# SCH_starcard_2025-07-30.net
KiCad netlist of a schematic drawn in EasyEDA
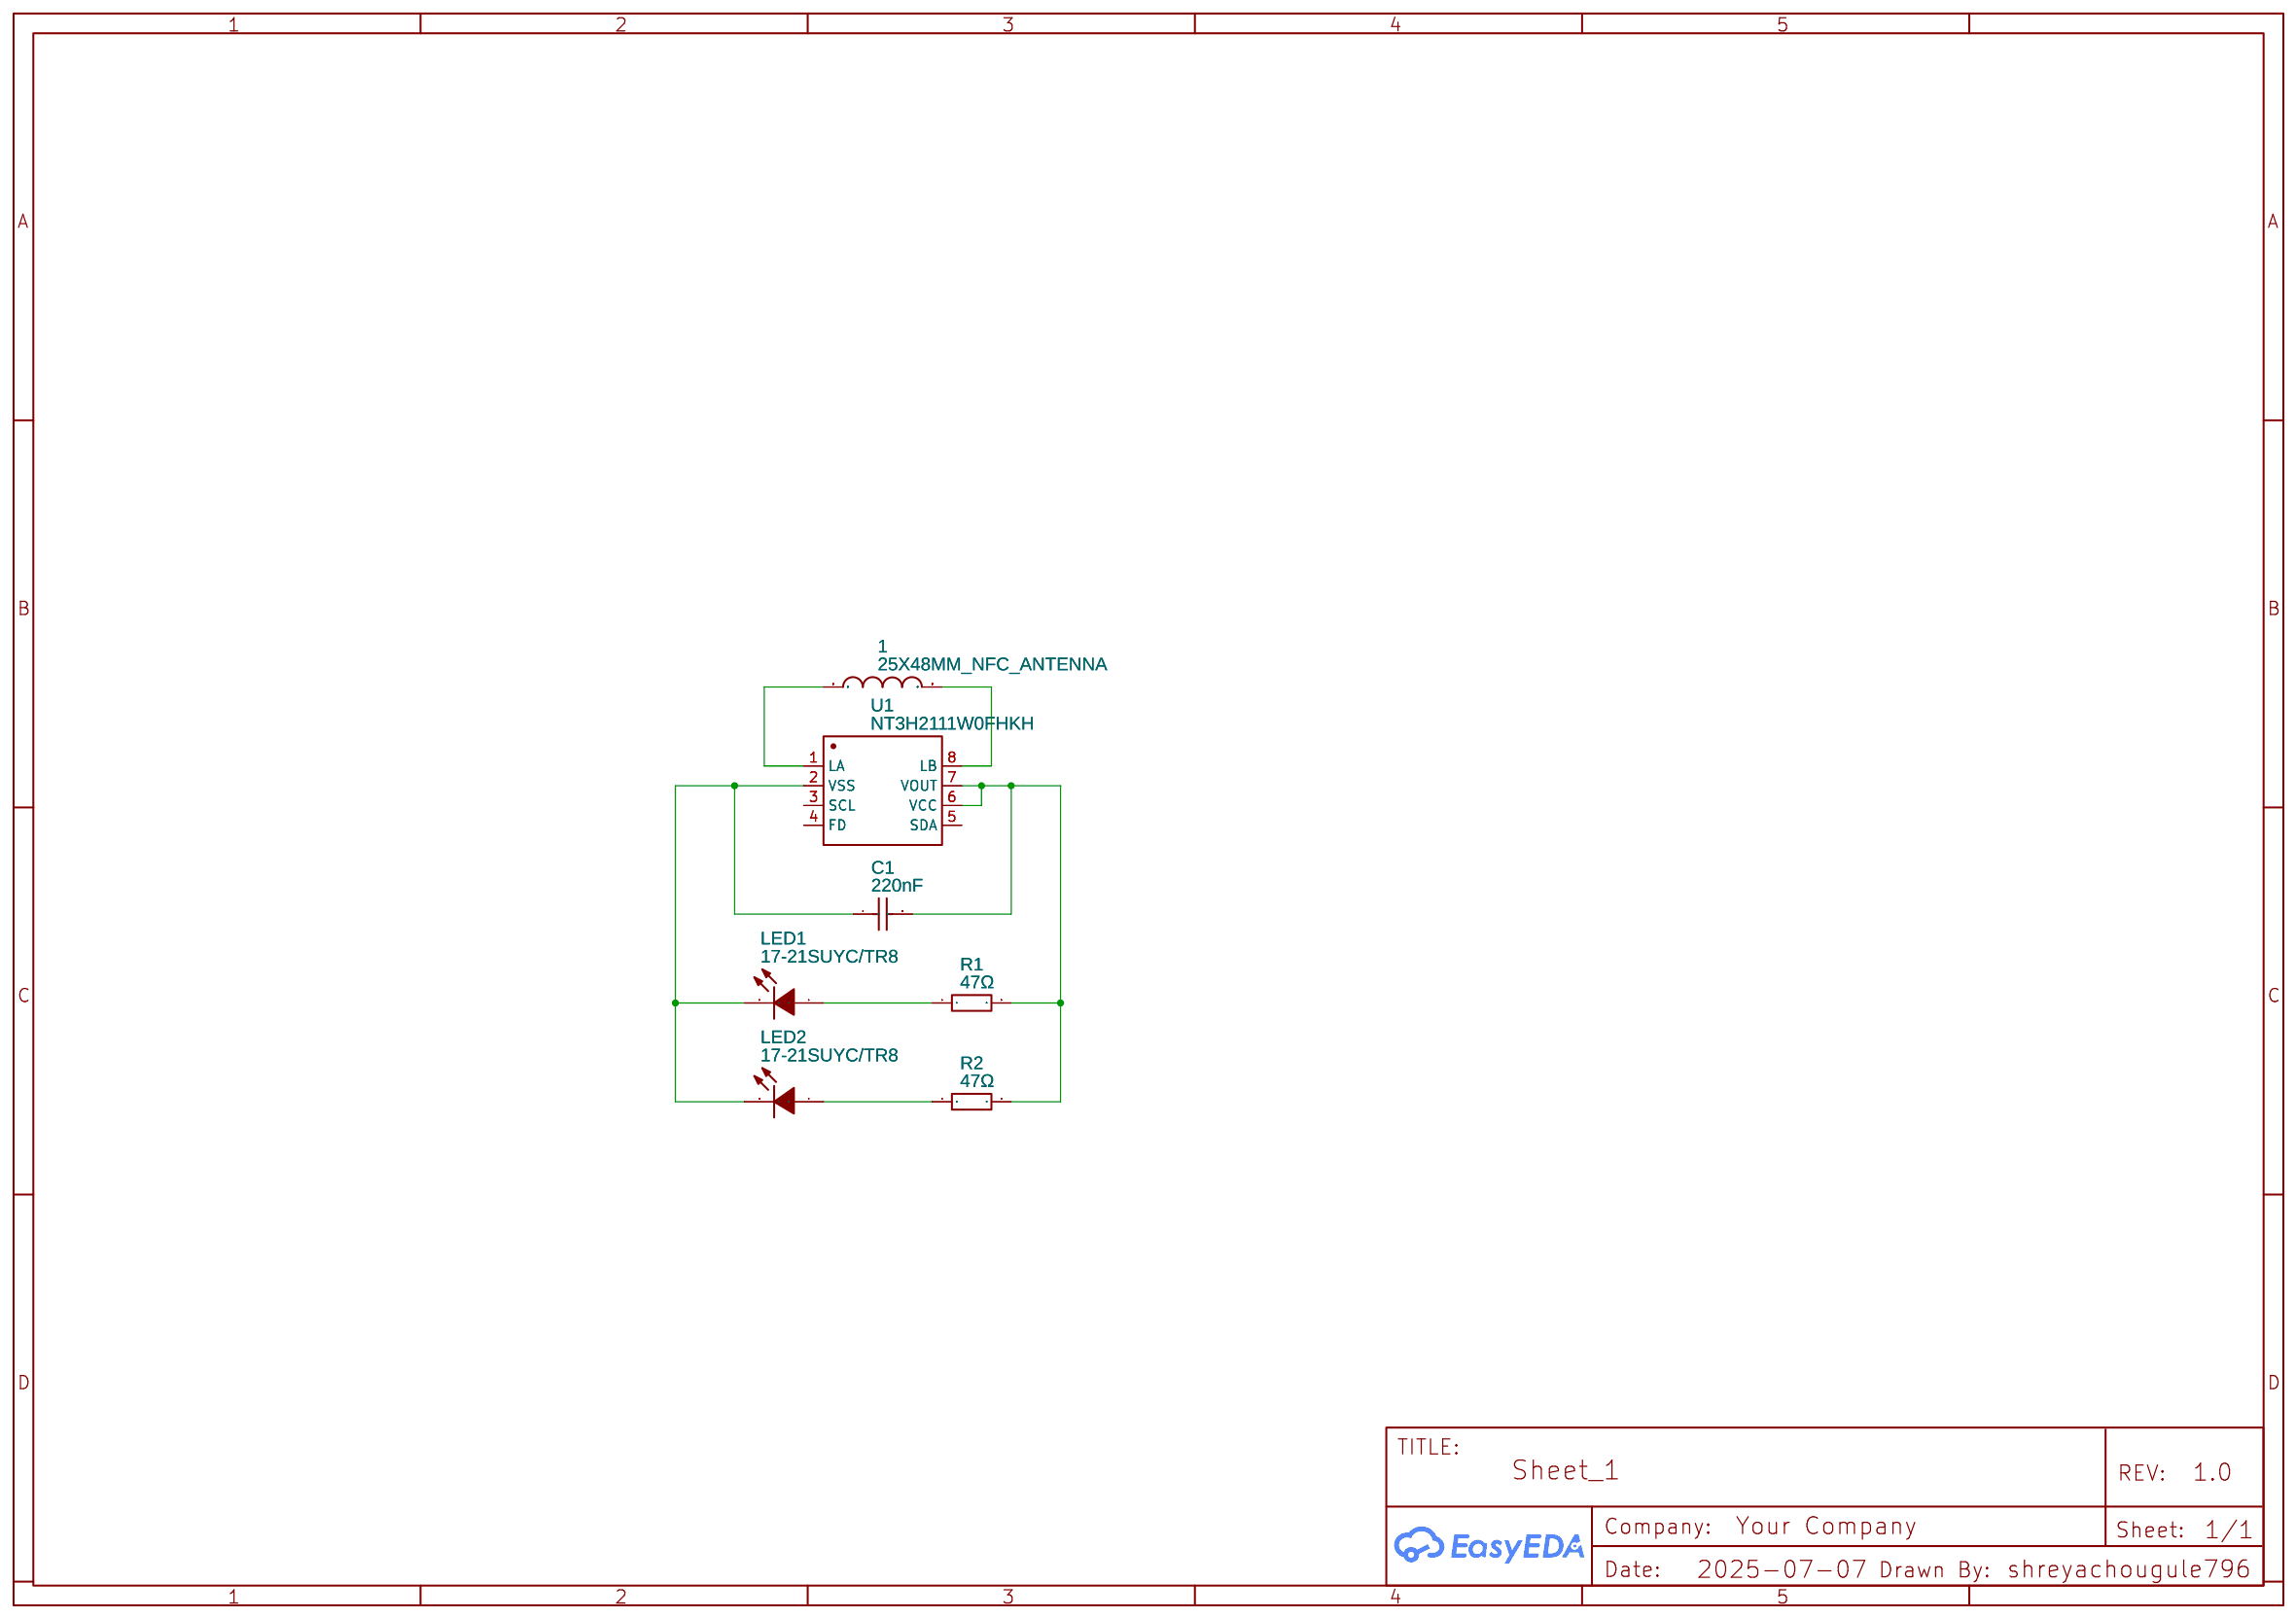
[diagram p0: schematic sheet]

(export (version "E")
  (design (tool "Eeschema 10.0.6"))
  (components
    (comp (ref "1") (value "25X48MM_NFC_ANTENNA") (libsource (lib "") (part "25X48MM_NFC_ANTENNA")))
    (comp (ref "C1")
      (value "220nF")
      (fields
        (field (name "Manufacturer Part") "CL10B224KA8NNNC")
        (field (name "Manufacturer") "SAMSUNG(三星)")
      )
      (libsource (lib "") (part "CL10B224KA8NNNC"))
    )
    (comp (ref "LED1")
      (value "17-21SUYC/TR8")
      (fields (field (name "Manufacturer Part") "KT-0805黄灯") (field (name "Manufacturer") "KENTO"))
      (libsource (lib "") (part "17-21SUYC/TR8"))
    )
    (comp (ref "LED2")
      (value "17-21SUYC/TR8")
      (fields (field (name "Manufacturer Part") "KT-0805黄灯") (field (name "Manufacturer") "KENTO"))
      (libsource (lib "") (part "17-21SUYC/TR8"))
    )
    (comp (ref "R1")
      (value "47Ω")
      (fields
        (field (name "Manufacturer Part") "0603WAF470JT5E")
        (field (name "Manufacturer") "UNI-ROYAL(厚声)")
      )
      (libsource (lib "") (part "0603WAF470JT5E"))
    )
    (comp (ref "R2")
      (value "47Ω")
      (fields
        (field (name "Manufacturer Part") "0603WAF470JT5E")
        (field (name "Manufacturer") "UNI-ROYAL(厚声)")
      )
      (libsource (lib "") (part "0603WAF470JT5E"))
    )
    (comp (ref "U1")
      (value "NT3H2111W0FHKH")
      (fields (field (name "Manufacturer") "NXP(恩智浦)"))
      (libsource (lib "") (part "NT3H2111W0FHKH"))
    )
  )
  (nets
    (net (code "1") (name "Net-(LED1-+)") (class "Default")
      (node (ref "LED1") (pin "1") (pinfunction "+_1") (pintype "unspecified"))
      (node (ref "R1") (pin "1") (pinfunction "1_1") (pintype "input"))
    )
    (net (code "2") (name "Net-(LED1--)") (class "Default")
      (node (ref "C1") (pin "1") (pinfunction "1_1") (pintype "input"))
      (node (ref "LED1") (pin "2") (pinfunction "-_2") (pintype "unspecified"))
      (node (ref "LED2") (pin "2") (pinfunction "-_2") (pintype "unspecified"))
      (node (ref "U1") (pin "2") (pinfunction "VSS_2") (pintype "unspecified"))
    )
    (net (code "3") (name "Net-(LED2-+)") (class "Default")
      (node (ref "LED2") (pin "1") (pinfunction "+_1") (pintype "unspecified"))
      (node (ref "R2") (pin "1") (pinfunction "1_1") (pintype "input"))
    )
    (net (code "4") (name "Net-(U1-LA)") (class "Default")
      (node (ref "1") (pin "P$1") (pinfunction "P$1_P$1") (pintype "bidirectional"))
      (node (ref "U1") (pin "1") (pinfunction "LA_1") (pintype "unspecified"))
    )
    (net (code "5") (name "Net-(U1-LB)") (class "Default")
      (node (ref "1") (pin "P$2") (pinfunction "P$2_P$2") (pintype "bidirectional"))
      (node (ref "U1") (pin "8") (pinfunction "LB_8") (pintype "unspecified"))
    )
    (net (code "6") (name "Net-(U1-VCC)") (class "Default")
      (node (ref "C1") (pin "2") (pinfunction "2_2") (pintype "input"))
      (node (ref "R1") (pin "2") (pinfunction "2_2") (pintype "input"))
      (node (ref "R2") (pin "2") (pinfunction "2_2") (pintype "input"))
      (node (ref "U1") (pin "6") (pinfunction "VCC_6") (pintype "unspecified"))
      (node (ref "U1") (pin "7") (pinfunction "VOUT_7") (pintype "unspecified"))
    )
    (net (code "7") (name "unconnected-(U1-FD-Pad4)") (class "Default")
      (node (ref "U1") (pin "4") (pinfunction "FD_4") (pintype "unspecified"))
    )
    (net (code "8") (name "unconnected-(U1-SCL-Pad3)") (class "Default")
      (node (ref "U1") (pin "3") (pinfunction "SCL_3") (pintype "unspecified"))
    )
    (net (code "9") (name "unconnected-(U1-SDA-Pad5)") (class "Default")
      (node (ref "U1") (pin "5") (pinfunction "SDA_5") (pintype "unspecified"))
    )
  )
)
